# Dc_motor_control.net
KiCad netlist of a schematic drawn in EAGLE
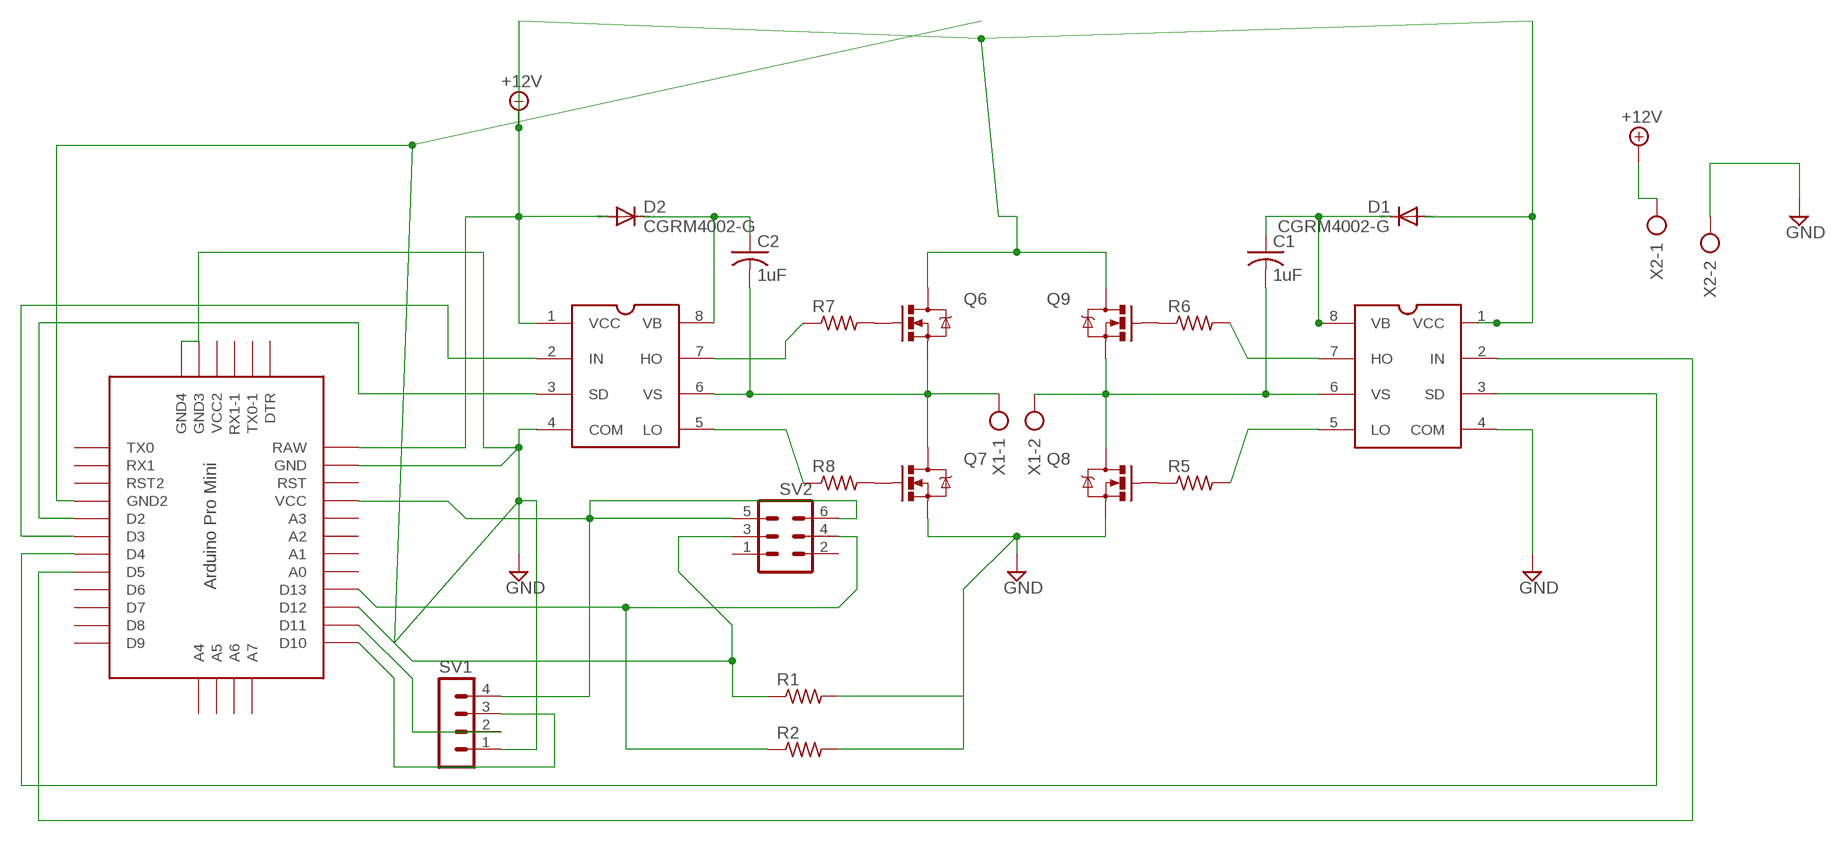
[diagram p0: schematic, sheet 1]

(export (version "E")
  (design (tool "Eeschema 10.0.6"))
  (components
    (comp (ref "C1")
      (value "1uF")
      (footprint "eagle-import:C1210")
      (libsource (lib "eagle-import") (part "C-USC1210"))
    )
    (comp (ref "C2")
      (value "1uF")
      (footprint "eagle-import:C1210")
      (libsource (lib "eagle-import") (part "C-USC1210"))
    )
    (comp (ref "D1")
      (value "CGRM4002-G")
      (footprint "eagle-import:SOD-123_MINI-SMA")
      (libsource (lib "eagle-import") (part "CGRM400-G2"))
    )
    (comp (ref "D2")
      (value "CGRM4002-G")
      (footprint "eagle-import:SOD-123_MINI-SMA")
      (libsource (lib "eagle-import") (part "CGRM400-G2"))
    )
    (comp (ref "Q6")
      (value "MOSFET-NCHANNELFDD8580")
      (footprint "eagle-import:DPAK")
      (libsource (lib "eagle-import") (part "MOSFET-NCHANNELFDD8580"))
    )
    (comp (ref "Q7")
      (value "MOSFET-NCHANNELFDD8580")
      (footprint "eagle-import:DPAK")
      (libsource (lib "eagle-import") (part "MOSFET-NCHANNELFDD8580"))
    )
    (comp (ref "Q8")
      (value "MOSFET-NCHANNELFDD8580")
      (footprint "eagle-import:DPAK")
      (libsource (lib "eagle-import") (part "MOSFET-NCHANNELFDD8580"))
    )
    (comp (ref "Q9")
      (value "MOSFET-NCHANNELFDD8580")
      (footprint "eagle-import:DPAK")
      (libsource (lib "eagle-import") (part "MOSFET-NCHANNELFDD8580"))
    )
    (comp (ref "R1")
      (value "R-US_R0402")
      (footprint "eagle-import:R0402")
      (libsource (lib "eagle-import") (part "R-US_R0402"))
    )
    (comp (ref "R2")
      (value "R-US_R0402")
      (footprint "eagle-import:R0402")
      (libsource (lib "eagle-import") (part "R-US_R0402"))
    )
    (comp (ref "R5")
      (value "R-US_R0402")
      (footprint "eagle-import:R0402")
      (libsource (lib "eagle-import") (part "R-US_R0402"))
    )
    (comp (ref "R6")
      (value "R-US_R0402")
      (footprint "eagle-import:R0402")
      (libsource (lib "eagle-import") (part "R-US_R0402"))
    )
    (comp (ref "R7")
      (value "R-US_R0402")
      (footprint "eagle-import:R0402")
      (libsource (lib "eagle-import") (part "R-US_R0402"))
    )
    (comp (ref "R8")
      (value "R-US_R0402")
      (footprint "eagle-import:R0402")
      (libsource (lib "eagle-import") (part "R-US_R0402"))
    )
    (comp (ref "SV1")
      (value "MA04-1")
      (footprint "eagle-import:MA04-1")
      (libsource (lib "eagle-import") (part "MA04-1"))
    )
    (comp (ref "SV2")
      (value "MA03-2")
      (footprint "eagle-import:MA03-2")
      (libsource (lib "eagle-import") (part "MA03-2"))
    )
    (comp (ref "U$1")
      (value "IR2104S")
      (footprint "eagle-import:IR2104S")
      (libsource (lib "eagle-import") (part "IR2104S"))
    )
    (comp (ref "U$2")
      (value "IR2104S")
      (footprint "eagle-import:IR2104S")
      (libsource (lib "eagle-import") (part "IR2104S"))
    )
    (comp (ref "U$3")
      (value "PRO-MINI")
      (footprint "eagle-import:PRO-MINI")
      (libsource (lib "eagle-import") (part "PRO-MINI"))
    )
    (comp (ref "X1")
      (value "AK500/2-H")
      (footprint "eagle-import:AK500_2-H")
      (libsource (lib "eagle-import") (part "AK500/2-H"))
    )
    (comp (ref "X2")
      (value "AK500/2-H")
      (footprint "eagle-import:AK500_2-H")
      (libsource (lib "eagle-import") (part "AK500/2-H"))
    )
  )
  (nets
    (net (code "1") (name "+12V") (class "Default")
      (node (ref "D1") (pin "A") (pinfunction "A_A") (pintype "passive"))
      (node (ref "D2") (pin "A") (pinfunction "A_A") (pintype "passive"))
      (node (ref "Q6") (pin "4") (pinfunction "D_4") (pintype "passive"))
      (node (ref "Q9") (pin "4") (pinfunction "D_4") (pintype "passive"))
      (node (ref "U$1") (pin "1") (pinfunction "VCC_1") (pintype "power_in"))
      (node (ref "U$2") (pin "1") (pinfunction "VCC_1") (pintype "power_in"))
      (node (ref "U$3") (pin "RAW") (pinfunction "RAW_RAW") (pintype "power_in"))
      (node (ref "X2") (pin "1") (pinfunction "KL_1") (pintype "passive"))
    )
    (net (code "2") (name "GND") (class "Default")
      (node (ref "Q7") (pin "3") (pinfunction "S_3") (pintype "passive"))
      (node (ref "Q8") (pin "3") (pinfunction "S_3") (pintype "passive"))
      (node (ref "R1") (pin "2") (pinfunction "2_2") (pintype "passive"))
      (node (ref "R2") (pin "2") (pinfunction "2_2") (pintype "passive"))
      (node (ref "SV1") (pin "1") (pinfunction "1_1") (pintype "passive"))
      (node (ref "U$1") (pin "4") (pinfunction "COM_4") (pintype "bidirectional"))
      (node (ref "U$2") (pin "4") (pinfunction "COM_4") (pintype "bidirectional"))
      (node (ref "U$3") (pin "GND") (pinfunction "GND_GND") (pintype "input"))
      (node (ref "U$3") (pin "GND1") (pinfunction "GND2_GND1") (pintype "bidirectional"))
      (node (ref "U$3") (pin "GND2") (pinfunction "GND4_GND2") (pintype "bidirectional"))
      (node (ref "U$3") (pin "GND3") (pinfunction "GND3_GND3") (pintype "bidirectional"))
      (node (ref "X2") (pin "2") (pinfunction "KL_2") (pintype "passive"))
    )
    (net (code "3") (name "Net-(Q6-G)") (class "Default")
      (node (ref "Q6") (pin "1") (pinfunction "G_1") (pintype "passive"))
      (node (ref "R7") (pin "2") (pinfunction "2_2") (pintype "passive"))
    )
    (net (code "4") (name "Net-(Q6-S)") (class "Default")
      (node (ref "C2") (pin "2") (pinfunction "2_2") (pintype "passive"))
      (node (ref "Q6") (pin "3") (pinfunction "S_3") (pintype "passive"))
      (node (ref "Q7") (pin "4") (pinfunction "D_4") (pintype "passive"))
      (node (ref "U$2") (pin "6") (pinfunction "VS_6") (pintype "power_in"))
      (node (ref "X1") (pin "1") (pinfunction "KL_1") (pintype "passive"))
    )
    (net (code "5") (name "Net-(Q7-G)") (class "Default")
      (node (ref "Q7") (pin "1") (pinfunction "G_1") (pintype "passive"))
      (node (ref "R8") (pin "2") (pinfunction "2_2") (pintype "passive"))
    )
    (net (code "6") (name "Net-(Q8-D)") (class "Default")
      (node (ref "C1") (pin "2") (pinfunction "2_2") (pintype "passive"))
      (node (ref "Q8") (pin "4") (pinfunction "D_4") (pintype "passive"))
      (node (ref "Q9") (pin "3") (pinfunction "S_3") (pintype "passive"))
      (node (ref "U$1") (pin "6") (pinfunction "VS_6") (pintype "power_in"))
      (node (ref "X1") (pin "2") (pinfunction "KL_2") (pintype "passive"))
    )
    (net (code "7") (name "Net-(Q8-G)") (class "Default")
      (node (ref "Q8") (pin "1") (pinfunction "G_1") (pintype "passive"))
      (node (ref "R5") (pin "1") (pinfunction "1_1") (pintype "passive"))
    )
    (net (code "8") (name "Net-(Q9-G)") (class "Default")
      (node (ref "Q9") (pin "1") (pinfunction "G_1") (pintype "passive"))
      (node (ref "R6") (pin "1") (pinfunction "1_1") (pintype "passive"))
    )
    (net (code "9") (name "Net-(R1-Pad1)") (class "Default")
      (node (ref "R1") (pin "1") (pinfunction "1_1") (pintype "passive"))
      (node (ref "SV2") (pin "3") (pinfunction "3_3") (pintype "passive"))
      (node (ref "U$3") (pin "D12") (pinfunction "D12_D12") (pintype "bidirectional"))
    )
    (net (code "10") (name "Net-(R2-Pad1)") (class "Default")
      (node (ref "R2") (pin "1") (pinfunction "1_1") (pintype "passive"))
      (node (ref "SV2") (pin "4") (pinfunction "4_4") (pintype "passive"))
      (node (ref "U$3") (pin "D13") (pinfunction "D13_D13") (pintype "bidirectional"))
    )
    (net (code "11") (name "Net-(SV1-Pad2)") (class "Default")
      (node (ref "SV1") (pin "2") (pinfunction "2_2") (pintype "passive"))
      (node (ref "U$3") (pin "D11") (pinfunction "D11_D11") (pintype "bidirectional"))
    )
    (net (code "12") (name "Net-(SV1-Pad3)") (class "Default")
      (node (ref "SV1") (pin "3") (pinfunction "3_3") (pintype "passive"))
      (node (ref "U$3") (pin "D10") (pinfunction "D10_D10") (pintype "bidirectional"))
    )
    (net (code "13") (name "Net-(SV1-Pad4)") (class "Default")
      (node (ref "SV1") (pin "4") (pinfunction "4_4") (pintype "passive"))
      (node (ref "SV2") (pin "5") (pinfunction "5_5") (pintype "passive"))
      (node (ref "SV2") (pin "6") (pinfunction "6_6") (pintype "passive"))
      (node (ref "U$3") (pin "VCC") (pinfunction "VCC_VCC") (pintype "bidirectional"))
    )
    (net (code "14") (name "Net-(U$1-HO)") (class "Default")
      (node (ref "R6") (pin "2") (pinfunction "2_2") (pintype "passive"))
      (node (ref "U$1") (pin "7") (pinfunction "HO_7") (pintype "bidirectional"))
    )
    (net (code "15") (name "Net-(U$1-IN)") (class "Default")
      (node (ref "U$1") (pin "2") (pinfunction "IN_2") (pintype "bidirectional"))
      (node (ref "U$3") (pin "D5") (pinfunction "D5_D5") (pintype "bidirectional"))
    )
    (net (code "16") (name "Net-(U$1-LO)") (class "Default")
      (node (ref "R5") (pin "2") (pinfunction "2_2") (pintype "passive"))
      (node (ref "U$1") (pin "5") (pinfunction "LO_5") (pintype "bidirectional"))
    )
    (net (code "17") (name "Net-(U$1-SD)") (class "Default")
      (node (ref "U$1") (pin "3") (pinfunction "SD_3") (pintype "bidirectional"))
      (node (ref "U$3") (pin "D4") (pinfunction "D4_D4") (pintype "bidirectional"))
    )
    (net (code "18") (name "Net-(U$1-VB)") (class "Default")
      (node (ref "C1") (pin "1") (pinfunction "1_1") (pintype "passive"))
      (node (ref "D1") (pin "C") (pinfunction "C_C") (pintype "passive"))
      (node (ref "U$1") (pin "8") (pinfunction "VB_8") (pintype "power_in"))
    )
    (net (code "19") (name "Net-(U$2-HO)") (class "Default")
      (node (ref "R7") (pin "1") (pinfunction "1_1") (pintype "passive"))
      (node (ref "U$2") (pin "7") (pinfunction "HO_7") (pintype "bidirectional"))
    )
    (net (code "20") (name "Net-(U$2-IN)") (class "Default")
      (node (ref "U$2") (pin "2") (pinfunction "IN_2") (pintype "bidirectional"))
      (node (ref "U$3") (pin "D3") (pinfunction "D3_D3") (pintype "bidirectional"))
    )
    (net (code "21") (name "Net-(U$2-LO)") (class "Default")
      (node (ref "R8") (pin "1") (pinfunction "1_1") (pintype "passive"))
      (node (ref "U$2") (pin "5") (pinfunction "LO_5") (pintype "bidirectional"))
    )
    (net (code "22") (name "Net-(U$2-SD)") (class "Default")
      (node (ref "U$2") (pin "3") (pinfunction "SD_3") (pintype "bidirectional"))
      (node (ref "U$3") (pin "D2") (pinfunction "D2_D2") (pintype "bidirectional"))
    )
    (net (code "23") (name "Net-(U$2-VB)") (class "Default")
      (node (ref "C2") (pin "1") (pinfunction "1_1") (pintype "passive"))
      (node (ref "D2") (pin "C") (pinfunction "C_C") (pintype "passive"))
      (node (ref "U$2") (pin "8") (pinfunction "VB_8") (pintype "power_in"))
    )
    (net (code "24") (name "unconnected-(SV2-Pad1)") (class "Default")
      (node (ref "SV2") (pin "1") (pinfunction "1_1") (pintype "passive"))
    )
    (net (code "25") (name "unconnected-(SV2-Pad2)") (class "Default")
      (node (ref "SV2") (pin "2") (pinfunction "2_2") (pintype "passive"))
    )
    (net (code "26") (name "unconnected-(U$3-PadA0)") (class "Default")
      (node (ref "U$3") (pin "A0") (pinfunction "A0_A0") (pintype "bidirectional"))
    )
    (net (code "27") (name "unconnected-(U$3-PadA1)") (class "Default")
      (node (ref "U$3") (pin "A1") (pinfunction "A1_A1") (pintype "bidirectional"))
    )
    (net (code "28") (name "unconnected-(U$3-PadA2)") (class "Default")
      (node (ref "U$3") (pin "A2") (pinfunction "A2_A2") (pintype "bidirectional"))
    )
    (net (code "29") (name "unconnected-(U$3-PadA3)") (class "Default")
      (node (ref "U$3") (pin "A3") (pinfunction "A3_A3") (pintype "bidirectional"))
    )
    (net (code "30") (name "unconnected-(U$3-PadA4)") (class "Default")
      (node (ref "U$3") (pin "A4") (pinfunction "A4_A4") (pintype "bidirectional"))
    )
    (net (code "31") (name "unconnected-(U$3-PadA5)") (class "Default")
      (node (ref "U$3") (pin "A5") (pinfunction "A5_A5") (pintype "bidirectional"))
    )
    (net (code "32") (name "unconnected-(U$3-PadA6)") (class "Default")
      (node (ref "U$3") (pin "A6") (pinfunction "A6_A6") (pintype "bidirectional"))
    )
    (net (code "33") (name "unconnected-(U$3-PadA7)") (class "Default")
      (node (ref "U$3") (pin "A7") (pinfunction "A7_A7") (pintype "bidirectional"))
    )
    (net (code "34") (name "unconnected-(U$3-PadD6)") (class "Default")
      (node (ref "U$3") (pin "D6") (pinfunction "D6_D6") (pintype "bidirectional"))
    )
    (net (code "35") (name "unconnected-(U$3-PadD7)") (class "Default")
      (node (ref "U$3") (pin "D7") (pinfunction "D7_D7") (pintype "bidirectional"))
    )
    (net (code "36") (name "unconnected-(U$3-PadD8)") (class "Default")
      (node (ref "U$3") (pin "D8") (pinfunction "D8_D8") (pintype "bidirectional"))
    )
    (net (code "37") (name "unconnected-(U$3-PadD9)") (class "Default")
      (node (ref "U$3") (pin "D9") (pinfunction "D9_D9") (pintype "bidirectional"))
    )
    (net (code "38") (name "unconnected-(U$3-PadDTR)") (class "Default")
      (node (ref "U$3") (pin "DTR") (pinfunction "DTR_DTR") (pintype "bidirectional"))
    )
    (net (code "39") (name "unconnected-(U$3-PadRST)") (class "Default")
      (node (ref "U$3") (pin "RST") (pinfunction "RST_RST") (pintype "bidirectional"))
    )
    (net (code "40") (name "unconnected-(U$3-PadRX1)") (class "Default")
      (node (ref "U$3") (pin "RX1") (pinfunction "RX1_RX1") (pintype "bidirectional"))
    )
    (net (code "41") (name "unconnected-(U$3-PadRX1-1)") (class "Default")
      (node (ref "U$3") (pin "RX1-1") (pinfunction "RX1-1_RX1-1") (pintype "bidirectional"))
    )
    (net (code "42") (name "unconnected-(U$3-PadTX0)") (class "Default")
      (node (ref "U$3") (pin "TX0") (pinfunction "TX0_TX0") (pintype "bidirectional"))
    )
    (net (code "43") (name "unconnected-(U$3-PadTX0-1)") (class "Default")
      (node (ref "U$3") (pin "TX0-1") (pinfunction "TX0-1_TX0-1") (pintype "bidirectional"))
    )
    (net (code "44") (name "unconnected-(U$3-RST2-PadRST1)") (class "Default")
      (node (ref "U$3") (pin "RST1") (pinfunction "RST2_RST1") (pintype "bidirectional"))
    )
    (net (code "45") (name "unconnected-(U$3-VCC2-PadVCC1)") (class "Default")
      (node (ref "U$3") (pin "VCC1") (pinfunction "VCC2_VCC1") (pintype "bidirectional"))
    )
  )
)
